# E-meter2.net
KiCad netlist of a schematic drawn in EAGLE
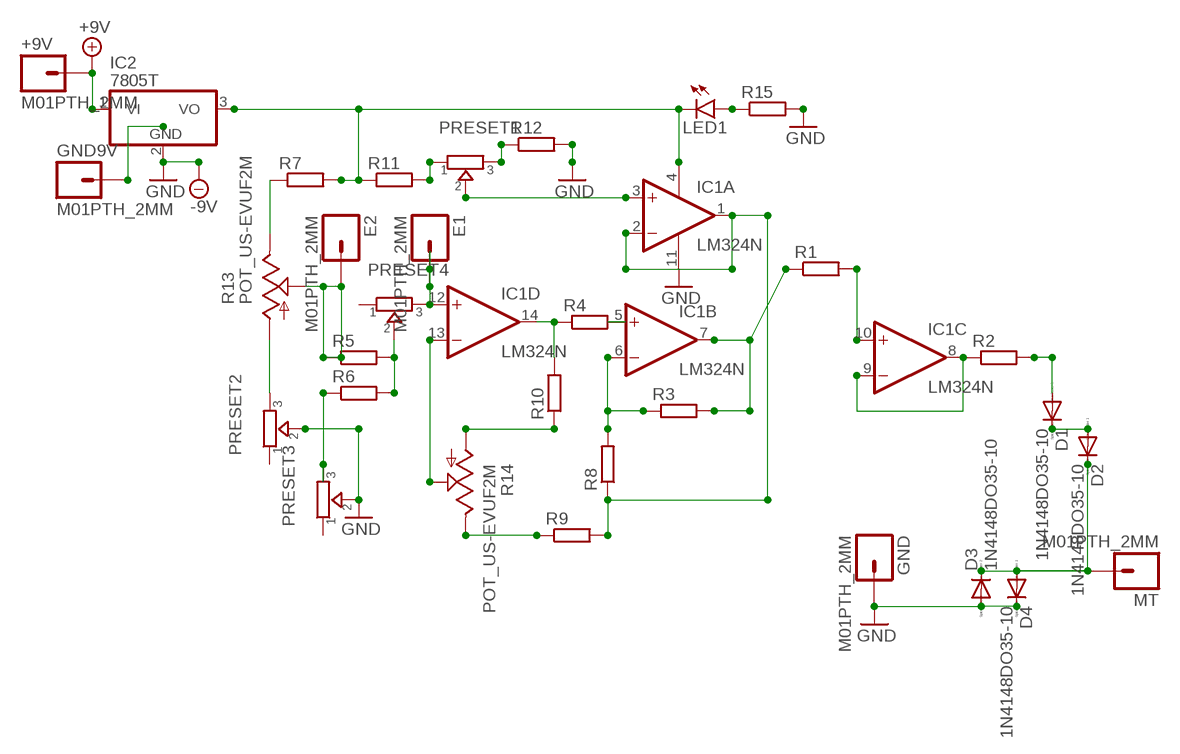
[diagram p0: schematic, sheet 1]

(export (version "E")
  (design (tool "Eeschema 10.0.6"))
  (components
    (comp (ref "+9V")
      (value "M01PTH_2MM")
      (footprint "eagle-import:1X01_2MM")
      (libsource (lib "eagle-import") (part "M01PTH_2MM"))
    )
    (comp (ref "D1")
      (value "1N4148DO35-10")
      (footprint "eagle-import:DO35-10")
      (libsource (lib "eagle-import") (part "1N4148DO35-10"))
    )
    (comp (ref "D2")
      (value "1N4148DO35-10")
      (footprint "eagle-import:DO35-10")
      (libsource (lib "eagle-import") (part "1N4148DO35-10"))
    )
    (comp (ref "D3")
      (value "1N4148DO35-10")
      (footprint "eagle-import:DO35-10")
      (libsource (lib "eagle-import") (part "1N4148DO35-10"))
    )
    (comp (ref "D4")
      (value "1N4148DO35-10")
      (footprint "eagle-import:DO35-10")
      (libsource (lib "eagle-import") (part "1N4148DO35-10"))
    )
    (comp (ref "E1")
      (value "M01PTH_2MM")
      (footprint "eagle-import:1X01_2MM")
      (libsource (lib "eagle-import") (part "M01PTH_2MM"))
    )
    (comp (ref "E2")
      (value "M01PTH_2MM")
      (footprint "eagle-import:1X01_2MM")
      (libsource (lib "eagle-import") (part "M01PTH_2MM"))
    )
    (comp (ref "GND")
      (value "M01PTH_2MM")
      (footprint "eagle-import:1X01_2MM")
      (libsource (lib "eagle-import") (part "M01PTH_2MM"))
    )
    (comp (ref "GND9V")
      (value "M01PTH_2MM")
      (footprint "eagle-import:1X01_2MM")
      (libsource (lib "eagle-import") (part "M01PTH_2MM"))
    )
    (comp (ref "IC1")
      (value "LM324N")
      (footprint "eagle-import:DIL14")
      (libsource (lib "eagle-import") (part "LM324N"))
    )
    (comp (ref "IC2")
      (value "7805T")
      (footprint "eagle-import:TO220H")
      (libsource (lib "eagle-import") (part "78T05"))
    )
    (comp (ref "LED1")
      (value "LED5MM")
      (footprint "eagle-import:LED5MM")
      (libsource (lib "eagle-import") (part "LED5MM"))
    )
    (comp (ref "MT")
      (value "M01PTH_2MM")
      (footprint "eagle-import:1X01_2MM")
      (libsource (lib "eagle-import") (part "M01PTH_2MM"))
    )
    (comp (ref "PRESET1")
      (value "TRIMMER-3306F")
      (footprint "eagle-import:TRIMMER_3306F")
      (libsource (lib "eagle-import") (part "TRIMMER-3306F"))
    )
    (comp (ref "PRESET2")
      (value "TRIMMER-3306F")
      (footprint "eagle-import:TRIMMER_3306F")
      (libsource (lib "eagle-import") (part "TRIMMER-3306F"))
    )
    (comp (ref "PRESET3")
      (value "TRIMMER-3306F")
      (footprint "eagle-import:TRIMMER_3306F")
      (libsource (lib "eagle-import") (part "TRIMMER-3306F"))
    )
    (comp (ref "PRESET4")
      (value "TRIMMER-3306F")
      (footprint "eagle-import:TRIMMER_3306F")
      (libsource (lib "eagle-import") (part "TRIMMER-3306F"))
    )
    (comp (ref "R1")
      (value "R-EU_0207/10")
      (footprint "eagle-import:0207_10")
      (libsource (lib "eagle-import") (part "R-EU_0207/10"))
    )
    (comp (ref "R2")
      (value "R-EU_0207/10")
      (footprint "eagle-import:0207_10")
      (libsource (lib "eagle-import") (part "R-EU_0207/10"))
    )
    (comp (ref "R3")
      (value "R-EU_0207/10")
      (footprint "eagle-import:0207_10")
      (libsource (lib "eagle-import") (part "R-EU_0207/10"))
    )
    (comp (ref "R4")
      (value "R-EU_0207/10")
      (footprint "eagle-import:0207_10")
      (libsource (lib "eagle-import") (part "R-EU_0207/10"))
    )
    (comp (ref "R5")
      (value "R-EU_0207/10")
      (footprint "eagle-import:0207_10")
      (libsource (lib "eagle-import") (part "R-EU_0207/10"))
    )
    (comp (ref "R6")
      (value "R-EU_0207/10")
      (footprint "eagle-import:0207_10")
      (libsource (lib "eagle-import") (part "R-EU_0207/10"))
    )
    (comp (ref "R7")
      (value "R-EU_0207/10")
      (footprint "eagle-import:0207_10")
      (libsource (lib "eagle-import") (part "R-EU_0207/10"))
    )
    (comp (ref "R8")
      (value "R-EU_0207/10")
      (footprint "eagle-import:0207_10")
      (libsource (lib "eagle-import") (part "R-EU_0207/10"))
    )
    (comp (ref "R9")
      (value "R-EU_0207/10")
      (footprint "eagle-import:0207_10")
      (libsource (lib "eagle-import") (part "R-EU_0207/10"))
    )
    (comp (ref "R10")
      (value "R-EU_0207/10")
      (footprint "eagle-import:0207_10")
      (libsource (lib "eagle-import") (part "R-EU_0207/10"))
    )
    (comp (ref "R11")
      (value "R-EU_0207/10")
      (footprint "eagle-import:0207_10")
      (libsource (lib "eagle-import") (part "R-EU_0207/10"))
    )
    (comp (ref "R12")
      (value "R-EU_0207/10")
      (footprint "eagle-import:0207_10")
      (libsource (lib "eagle-import") (part "R-EU_0207/10"))
    )
    (comp (ref "R13")
      (value "POT_US-EVUF2M")
      (footprint "eagle-import:POT_EVUFXM")
      (libsource (lib "eagle-import") (part "POT_US-EVUMF2"))
    )
    (comp (ref "R14")
      (value "POT_US-EVUF2M")
      (footprint "eagle-import:POT_EVUFXM")
      (libsource (lib "eagle-import") (part "POT_US-EVUMF2"))
    )
    (comp (ref "R15")
      (value "R-EU_0207/10")
      (footprint "eagle-import:0207_10")
      (libsource (lib "eagle-import") (part "R-EU_0207/10"))
    )
  )
  (nets
    (net (code "1") (name "+9V") (class "Default")
      (node (ref "+9V") (pin "1") (pinfunction "1_1") (pintype "passive"))
      (node (ref "IC2") (pin "1") (pinfunction "VI_1") (pintype "input"))
    )
    (net (code "2") (name "-9V") (class "Default")
      (node (ref "D3") (pin "A") (pinfunction "A_A") (pintype "passive"))
      (node (ref "D4") (pin "C") (pinfunction "C_C") (pintype "passive"))
      (node (ref "GND") (pin "1") (pinfunction "1_1") (pintype "passive"))
      (node (ref "IC1") (pin "11") (pinfunction "V-_11") (pintype "power_in"))
      (node (ref "IC2") (pin "2") (pinfunction "GND_2") (pintype "passive"))
      (node (ref "PRESET2") (pin "2") (pinfunction "2_2") (pintype "passive"))
      (node (ref "PRESET3") (pin "2") (pinfunction "2_2") (pintype "passive"))
      (node (ref "R12") (pin "2") (pinfunction "2_2") (pintype "passive"))
      (node (ref "R15") (pin "2") (pinfunction "2_2") (pintype "passive"))
    )
    (net (code "3") (name "Net-(D1-PadA)") (class "Default")
      (node (ref "D1") (pin "A") (pinfunction "A_A") (pintype "passive"))
      (node (ref "R2") (pin "2") (pinfunction "2_2") (pintype "passive"))
    )
    (net (code "4") (name "Net-(D1-PadC)") (class "Default")
      (node (ref "D1") (pin "C") (pinfunction "C_C") (pintype "passive"))
      (node (ref "D2") (pin "A") (pinfunction "A_A") (pintype "passive"))
    )
    (net (code "5") (name "Net-(D2-PadC)") (class "Default")
      (node (ref "D2") (pin "C") (pinfunction "C_C") (pintype "passive"))
      (node (ref "D3") (pin "C") (pinfunction "C_C") (pintype "passive"))
      (node (ref "D4") (pin "A") (pinfunction "A_A") (pintype "passive"))
      (node (ref "MT") (pin "1") (pinfunction "1_1") (pintype "passive"))
    )
    (net (code "6") (name "Net-(IC1A-+IN)") (class "Default")
      (node (ref "IC1") (pin "3") (pinfunction "+IN_3") (pintype "input"))
      (node (ref "PRESET1") (pin "2") (pinfunction "2_2") (pintype "passive"))
    )
    (net (code "7") (name "Net-(IC1A--IN)") (class "Default")
      (node (ref "IC1") (pin "1") (pinfunction "OUT_1") (pintype "output"))
      (node (ref "IC1") (pin "2") (pinfunction "-IN_2") (pintype "input"))
      (node (ref "R8") (pin "1") (pinfunction "1_1") (pintype "passive"))
      (node (ref "R9") (pin "2") (pinfunction "2_2") (pintype "passive"))
    )
    (net (code "8") (name "Net-(IC1B-+IN)") (class "Default")
      (node (ref "IC1") (pin "5") (pinfunction "+IN_5") (pintype "input"))
      (node (ref "R4") (pin "2") (pinfunction "2_2") (pintype "passive"))
    )
    (net (code "9") (name "Net-(IC1B--IN)") (class "Default")
      (node (ref "IC1") (pin "6") (pinfunction "-IN_6") (pintype "input"))
      (node (ref "R3") (pin "1") (pinfunction "1_1") (pintype "passive"))
      (node (ref "R8") (pin "2") (pinfunction "2_2") (pintype "passive"))
    )
    (net (code "10") (name "Net-(IC1B-OUT)") (class "Default")
      (node (ref "IC1") (pin "7") (pinfunction "OUT_7") (pintype "output"))
      (node (ref "R1") (pin "1") (pinfunction "1_1") (pintype "passive"))
      (node (ref "R3") (pin "2") (pinfunction "2_2") (pintype "passive"))
    )
    (net (code "11") (name "Net-(IC1C-+IN)") (class "Default")
      (node (ref "IC1") (pin "10") (pinfunction "+IN_10") (pintype "input"))
      (node (ref "R1") (pin "2") (pinfunction "2_2") (pintype "passive"))
    )
    (net (code "12") (name "Net-(IC1C--IN)") (class "Default")
      (node (ref "IC1") (pin "8") (pinfunction "OUT_8") (pintype "output"))
      (node (ref "IC1") (pin "9") (pinfunction "-IN_9") (pintype "input"))
      (node (ref "R2") (pin "1") (pinfunction "1_1") (pintype "passive"))
    )
    (net (code "13") (name "Net-(IC1D-+IN)") (class "Default")
      (node (ref "E1") (pin "1") (pinfunction "1_1") (pintype "passive"))
      (node (ref "IC1") (pin "12") (pinfunction "+IN_12") (pintype "input"))
      (node (ref "PRESET4") (pin "3") (pinfunction "3_3") (pintype "passive"))
    )
    (net (code "14") (name "Net-(IC1D--IN)") (class "Default")
      (node (ref "IC1") (pin "13") (pinfunction "-IN_13") (pintype "input"))
      (node (ref "R14") (pin "2") (pinfunction "S_2") (pintype "passive"))
    )
    (net (code "15") (name "Net-(IC1D-OUT)") (class "Default")
      (node (ref "IC1") (pin "14") (pinfunction "OUT_14") (pintype "output"))
      (node (ref "R10") (pin "2") (pinfunction "2_2") (pintype "passive"))
      (node (ref "R4") (pin "1") (pinfunction "1_1") (pintype "passive"))
    )
    (net (code "16") (name "Net-(IC1E-V+)") (class "Default")
      (node (ref "IC1") (pin "4") (pinfunction "V+_4") (pintype "power_in"))
      (node (ref "IC2") (pin "3") (pinfunction "VO_3") (pintype "passive"))
      (node (ref "LED1") (pin "K") (pinfunction "C_K") (pintype "passive"))
      (node (ref "R11") (pin "1") (pinfunction "1_1") (pintype "passive"))
      (node (ref "R7") (pin "2") (pinfunction "2_2") (pintype "passive"))
    )
    (net (code "17") (name "Net-(LED1-PadA)") (class "Default")
      (node (ref "LED1") (pin "A") (pinfunction "A_A") (pintype "passive"))
      (node (ref "R15") (pin "1") (pinfunction "1_1") (pintype "passive"))
    )
    (net (code "18") (name "Net-(PRESET1-Pad1)") (class "Default")
      (node (ref "PRESET1") (pin "1") (pinfunction "1_1") (pintype "passive"))
      (node (ref "R11") (pin "2") (pinfunction "2_2") (pintype "passive"))
    )
    (net (code "19") (name "Net-(PRESET1-Pad3)") (class "Default")
      (node (ref "PRESET1") (pin "3") (pinfunction "3_3") (pintype "passive"))
      (node (ref "R12") (pin "1") (pinfunction "1_1") (pintype "passive"))
    )
    (net (code "20") (name "Net-(PRESET3-Pad3)") (class "Default")
      (node (ref "PRESET3") (pin "3") (pinfunction "3_3") (pintype "passive"))
      (node (ref "R6") (pin "1") (pinfunction "1_1") (pintype "passive"))
    )
    (net (code "21") (name "Net-(PRESET4-Pad2)") (class "Default")
      (node (ref "PRESET4") (pin "2") (pinfunction "2_2") (pintype "passive"))
      (node (ref "R5") (pin "2") (pinfunction "2_2") (pintype "passive"))
      (node (ref "R6") (pin "2") (pinfunction "2_2") (pintype "passive"))
    )
    (net (code "22") (name "Net-(R13-A)") (class "Default")
      (node (ref "PRESET2") (pin "3") (pinfunction "3_3") (pintype "passive"))
      (node (ref "R13") (pin "1") (pinfunction "A_1") (pintype "passive"))
    )
    (net (code "23") (name "Net-(R13-E)") (class "Default")
      (node (ref "R13") (pin "3") (pinfunction "E_3") (pintype "passive"))
      (node (ref "R7") (pin "1") (pinfunction "1_1") (pintype "passive"))
    )
    (net (code "24") (name "Net-(R13-S)") (class "Default")
      (node (ref "E2") (pin "1") (pinfunction "1_1") (pintype "passive"))
      (node (ref "R13") (pin "2") (pinfunction "S_2") (pintype "passive"))
      (node (ref "R5") (pin "1") (pinfunction "1_1") (pintype "passive"))
    )
    (net (code "25") (name "Net-(R14-A)") (class "Default")
      (node (ref "R10") (pin "1") (pinfunction "1_1") (pintype "passive"))
      (node (ref "R14") (pin "1") (pinfunction "A_1") (pintype "passive"))
    )
    (net (code "26") (name "Net-(R14-E)") (class "Default")
      (node (ref "R14") (pin "3") (pinfunction "E_3") (pintype "passive"))
      (node (ref "R9") (pin "1") (pinfunction "1_1") (pintype "passive"))
    )
    (net (code "27") (name "unconnected-(GND9V-Pad1)") (class "Default")
      (node (ref "GND9V") (pin "1") (pinfunction "1_1") (pintype "passive"))
    )
    (net (code "28") (name "unconnected-(PRESET2-Pad1)") (class "Default")
      (node (ref "PRESET2") (pin "1") (pinfunction "1_1") (pintype "passive"))
    )
    (net (code "29") (name "unconnected-(PRESET3-Pad1)") (class "Default")
      (node (ref "PRESET3") (pin "1") (pinfunction "1_1") (pintype "passive"))
    )
    (net (code "30") (name "unconnected-(PRESET4-Pad1)") (class "Default")
      (node (ref "PRESET4") (pin "1") (pinfunction "1_1") (pintype "passive"))
    )
  )
)
